# Arduino_1_0.net
KiCad netlist of a schematic drawn in EAGLE
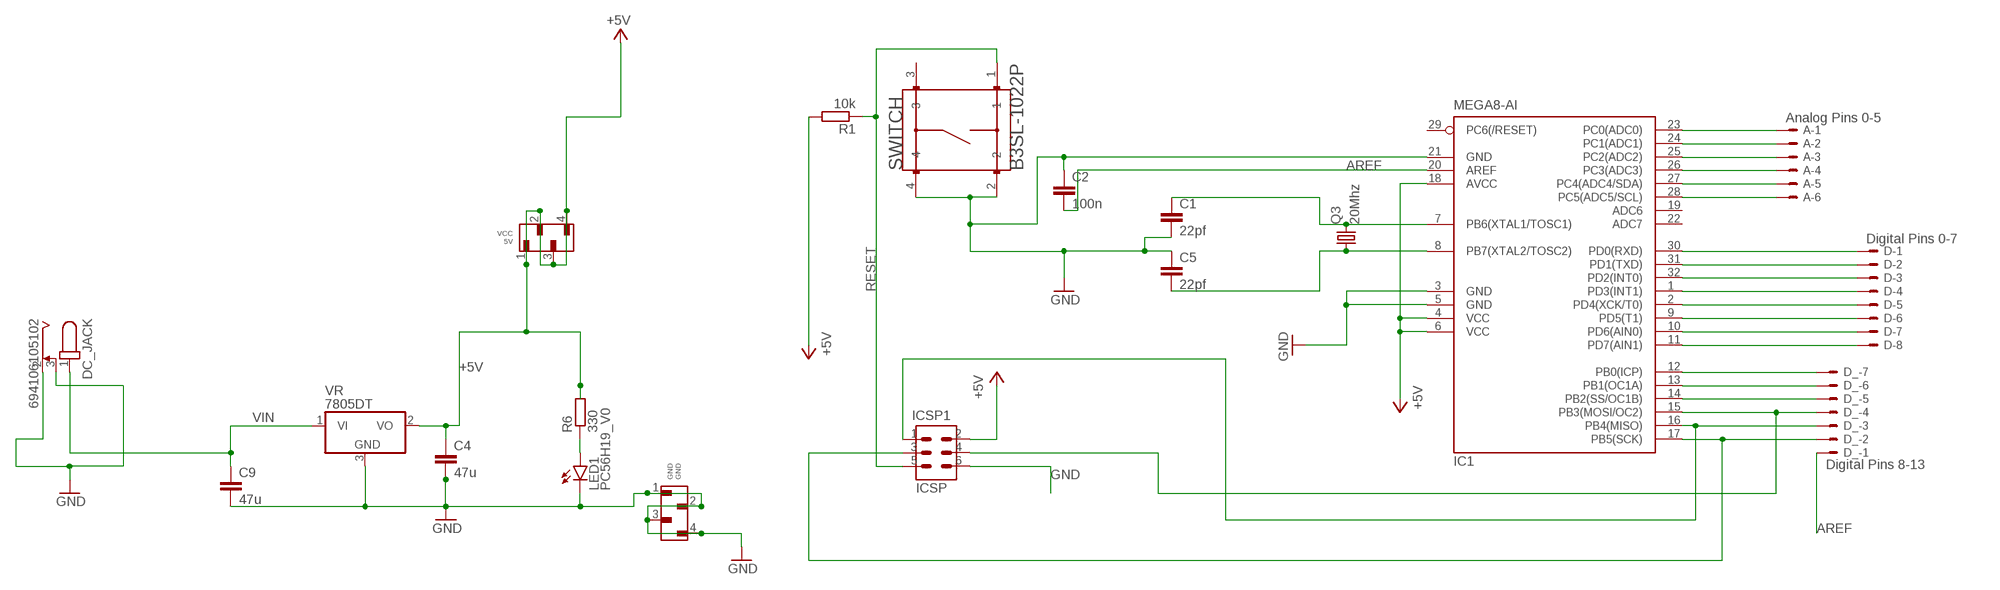
[diagram p0: schematic, sheet 1]

(export (version "E")
  (design (tool "Eeschema 10.0.6"))
  (components
    (comp (ref "A")
      (value "Analog Pins 0-5")
      (footprint "eagle-import:87438-06")
      (fields (field (name "MF") "MOLEX") (field (name "MPN") "87438-0643"))
      (libsource (lib "eagle-import") (part "87438-06"))
    )
    (comp (ref "C1")
      (value "22pf")
      (footprint "eagle-import:C0805")
      (libsource (lib "eagle-import") (part "C-EUC0805"))
    )
    (comp (ref "C2")
      (value "100n")
      (footprint "eagle-import:C0805")
      (libsource (lib "eagle-import") (part "C-EUC0805"))
    )
    (comp (ref "C4")
      (value "47u")
      (footprint "eagle-import:C0805")
      (libsource (lib "eagle-import") (part "C-EUC0805"))
    )
    (comp (ref "C5")
      (value "22pf")
      (footprint "eagle-import:C0805")
      (libsource (lib "eagle-import") (part "C-EUC0805"))
    )
    (comp (ref "C9")
      (value "47u")
      (footprint "eagle-import:C0805")
      (libsource (lib "eagle-import") (part "C-EUC0805"))
    )
    (comp (ref "D")
      (value "Digital Pins 0-7")
      (footprint "eagle-import:87438-08")
      (fields (field (name "MF") "MOLEX"))
      (libsource (lib "eagle-import") (part "87438-08"))
    )
    (comp (ref "DC_JACK")
      (value "694106105102")
      (footprint "eagle-import:694106105102")
      (fields
        (field (name "DIGIKEY_PART_NUMBER") "732-5928-2-ND")
        (field (name "MANUFACTURER") "Wurth Electronics Inc.")
        (field (name "CREATED_BY") "PCBLayout.com")
      )
      (libsource (lib "eagle-import") (part "694106105102"))
    )
    (comp (ref "D_")
      (value "Digital Pins 8-13")
      (footprint "eagle-import:87438-07")
      (fields (field (name "MF") "WALDOM/MOLEX") (field (name "MPN") "87438-0733"))
      (libsource (lib "eagle-import") (part "87438-07"))
    )
    (comp (ref "GND")
      (value "GND")
      (footprint "eagle-import:61000418221")
      (libsource (lib "eagle-import") (part "6100XX18221_61000418221"))
    )
    (comp (ref "IC1")
      (value "MEGA8-AI")
      (footprint "eagle-import:TQFP32-08")
      (fields (field (name "MPN") "ATMEGA8-16AU"))
      (libsource (lib "eagle-import") (part "MEGA8-AI"))
    )
    (comp (ref "ICSP1")
      (value "ICSP")
      (footprint "eagle-import:621006245821")
      (fields
        (field (name "MANUFACTURER") "Wurth Elektronik")
        (field (name "MPN") "621006245821")
        (field (name "CREATED_BY") "PCBLayout.com")
      )
      (libsource (lib "eagle-import") (part "621006245821"))
    )
    (comp (ref "LED1")
      (value "PC56H19_V0")
      (footprint "eagle-import:PC56H19_V0")
      (libsource (lib "eagle-import") (part "PC56H19_V0"))
    )
    (comp (ref "Q3")
      (value "20Mhz")
      (footprint "eagle-import:FC-12M")
      (libsource (lib "eagle-import") (part "FC-12M"))
    )
    (comp (ref "R1")
      (value "10k")
      (footprint "eagle-import:M0805")
      (libsource (lib "eagle-import") (part "R-EU_M0805"))
    )
    (comp (ref "R6")
      (value "330")
      (footprint "eagle-import:M0805")
      (libsource (lib "eagle-import") (part "R-EU_M0805"))
    )
    (comp (ref "SWITCH")
      (value "B3SL-1022P")
      (footprint "eagle-import:SW_B3SL-1022P")
      (fields (field (name "MF") "Omron"))
      (libsource (lib "eagle-import") (part "B3SL-1022P"))
    )
    (comp (ref "VCC")
      (value "5V")
      (footprint "eagle-import:61000418221")
      (libsource (lib "eagle-import") (part "6100XX18221_61000418221"))
    )
    (comp (ref "VR")
      (value "7805DT")
      (footprint "eagle-import:TO252")
      (libsource (lib "eagle-import") (part "78DT05"))
    )
  )
  (nets
    (net (code "1") (name "+5V") (class "Default")
      (node (ref "C4") (pin "1") (pinfunction "1_1") (pintype "passive"))
      (node (ref "IC1") (pin "18") (pinfunction "AVCC_18") (pintype "power_in"))
      (node (ref "IC1") (pin "4") (pinfunction "VCC_4") (pintype "power_in"))
      (node (ref "IC1") (pin "6") (pinfunction "VCC_6") (pintype "power_in"))
      (node (ref "ICSP1") (pin "2") (pinfunction "2_2") (pintype "passive"))
      (node (ref "R1") (pin "2") (pinfunction "2_2") (pintype "passive"))
      (node (ref "R6") (pin "2") (pinfunction "2_2") (pintype "passive"))
      (node (ref "VCC") (pin "1") (pinfunction "1_1") (pintype "passive"))
      (node (ref "VCC") (pin "2") (pinfunction "2_2") (pintype "passive"))
      (node (ref "VCC") (pin "3") (pinfunction "3_3") (pintype "passive"))
      (node (ref "VCC") (pin "4") (pinfunction "4_4") (pintype "passive"))
      (node (ref "VR") (pin "2") (pinfunction "VO_2") (pintype "passive"))
    )
    (net (code "2") (name "/AREF") (class "Default")
      (node (ref "C2") (pin "2") (pinfunction "2_2") (pintype "passive"))
      (node (ref "D_") (pin "1") (pinfunction "S_1") (pintype "passive"))
      (node (ref "IC1") (pin "20") (pinfunction "AREF_20") (pintype "passive"))
    )
    (net (code "3") (name "/RESET") (class "Default")
      (node (ref "ICSP1") (pin "5") (pinfunction "5_5") (pintype "passive"))
      (node (ref "R1") (pin "1") (pinfunction "1_1") (pintype "passive"))
      (node (ref "SWITCH") (pin "1") (pinfunction "1_1") (pintype "passive"))
    )
    (net (code "4") (name "/VIN") (class "Default")
      (node (ref "C9") (pin "1") (pinfunction "1_1") (pintype "passive"))
      (node (ref "DC_JACK") (pin "1") (pinfunction "1_1") (pintype "passive"))
      (node (ref "VR") (pin "1") (pinfunction "VI_1") (pintype "input"))
    )
    (net (code "5") (name "GND") (class "Default")
      (node (ref "C1") (pin "2") (pinfunction "2_2") (pintype "passive"))
      (node (ref "C2") (pin "1") (pinfunction "1_1") (pintype "passive"))
      (node (ref "C4") (pin "2") (pinfunction "2_2") (pintype "passive"))
      (node (ref "C5") (pin "1") (pinfunction "1_1") (pintype "passive"))
      (node (ref "C9") (pin "2") (pinfunction "2_2") (pintype "passive"))
      (node (ref "DC_JACK") (pin "2") (pinfunction "2_2") (pintype "passive"))
      (node (ref "DC_JACK") (pin "3") (pinfunction "3_3") (pintype "passive"))
      (node (ref "GND") (pin "1") (pinfunction "1_1") (pintype "passive"))
      (node (ref "GND") (pin "2") (pinfunction "2_2") (pintype "passive"))
      (node (ref "GND") (pin "3") (pinfunction "3_3") (pintype "passive"))
      (node (ref "GND") (pin "4") (pinfunction "4_4") (pintype "passive"))
      (node (ref "IC1") (pin "21") (pinfunction "GND_21") (pintype "power_in"))
      (node (ref "IC1") (pin "3") (pinfunction "GND_3") (pintype "power_in"))
      (node (ref "IC1") (pin "5") (pinfunction "GND_5") (pintype "power_in"))
      (node (ref "ICSP1") (pin "6") (pinfunction "6_6") (pintype "passive"))
      (node (ref "LED1") (pin "1") (pinfunction "C_1") (pintype "passive"))
      (node (ref "LED1") (pin "3") (pinfunction "C_3") (pintype "passive"))
      (node (ref "SWITCH") (pin "2") (pinfunction "2_2") (pintype "passive"))
      (node (ref "SWITCH") (pin "4") (pinfunction "4_4") (pintype "passive"))
      (node (ref "VR") (pin "3") (pinfunction "GND_3") (pintype "passive"))
    )
    (net (code "6") (name "Net-(AA-S)") (class "Default")
      (node (ref "A") (pin "1") (pinfunction "S_1") (pintype "passive"))
      (node (ref "IC1") (pin "23") (pinfunction "PC0(ADC0)_23") (pintype "bidirectional"))
    )
    (net (code "7") (name "Net-(AB-S)") (class "Default")
      (node (ref "A") (pin "2") (pinfunction "S_2") (pintype "passive"))
      (node (ref "IC1") (pin "24") (pinfunction "PC1(ADC1)_24") (pintype "bidirectional"))
    )
    (net (code "8") (name "Net-(AC-S)") (class "Default")
      (node (ref "A") (pin "3") (pinfunction "S_3") (pintype "passive"))
      (node (ref "IC1") (pin "25") (pinfunction "PC2(ADC2)_25") (pintype "bidirectional"))
    )
    (net (code "9") (name "Net-(AD-S)") (class "Default")
      (node (ref "A") (pin "4") (pinfunction "S_4") (pintype "passive"))
      (node (ref "IC1") (pin "26") (pinfunction "PC3(ADC3)_26") (pintype "bidirectional"))
    )
    (net (code "10") (name "Net-(AE-S)") (class "Default")
      (node (ref "A") (pin "5") (pinfunction "S_5") (pintype "passive"))
      (node (ref "IC1") (pin "27") (pinfunction "PC4(ADC4/SDA)_27") (pintype "bidirectional"))
    )
    (net (code "11") (name "Net-(AF-S)") (class "Default")
      (node (ref "A") (pin "6") (pinfunction "S_6") (pintype "passive"))
      (node (ref "IC1") (pin "28") (pinfunction "PC5(ADC5/SCL)_28") (pintype "bidirectional"))
    )
    (net (code "12") (name "Net-(DA-S)") (class "Default")
      (node (ref "D") (pin "1") (pinfunction "S_1") (pintype "passive"))
      (node (ref "IC1") (pin "30") (pinfunction "PD0(RXD)_30") (pintype "bidirectional"))
    )
    (net (code "13") (name "Net-(DB-S)") (class "Default")
      (node (ref "D") (pin "2") (pinfunction "S_2") (pintype "passive"))
      (node (ref "IC1") (pin "31") (pinfunction "PD1(TXD)_31") (pintype "bidirectional"))
    )
    (net (code "14") (name "Net-(DC-S)") (class "Default")
      (node (ref "D") (pin "3") (pinfunction "S_3") (pintype "passive"))
      (node (ref "IC1") (pin "32") (pinfunction "PD2(INT0)_32") (pintype "bidirectional"))
    )
    (net (code "15") (name "Net-(DD-S)") (class "Default")
      (node (ref "D") (pin "4") (pinfunction "S_4") (pintype "passive"))
      (node (ref "IC1") (pin "1") (pinfunction "PD3(INT1)_1") (pintype "bidirectional"))
    )
    (net (code "16") (name "Net-(DE-S)") (class "Default")
      (node (ref "D") (pin "5") (pinfunction "S_5") (pintype "passive"))
      (node (ref "IC1") (pin "2") (pinfunction "PD4(XCK/T0)_2") (pintype "bidirectional"))
    )
    (net (code "17") (name "Net-(DF-S)") (class "Default")
      (node (ref "D") (pin "6") (pinfunction "S_6") (pintype "passive"))
      (node (ref "IC1") (pin "9") (pinfunction "PD5(T1)_9") (pintype "bidirectional"))
    )
    (net (code "18") (name "Net-(DG-S)") (class "Default")
      (node (ref "D") (pin "7") (pinfunction "S_7") (pintype "passive"))
      (node (ref "IC1") (pin "10") (pinfunction "PD6(AIN0)_10") (pintype "bidirectional"))
    )
    (net (code "19") (name "Net-(DH-S)") (class "Default")
      (node (ref "D") (pin "8") (pinfunction "S_8") (pintype "passive"))
      (node (ref "IC1") (pin "11") (pinfunction "PD7(AIN1)_11") (pintype "bidirectional"))
    )
    (net (code "20") (name "Net-(D_B-S)") (class "Default")
      (node (ref "D_") (pin "2") (pinfunction "S_2") (pintype "passive"))
      (node (ref "IC1") (pin "17") (pinfunction "PB5(SCK)_17") (pintype "bidirectional"))
      (node (ref "ICSP1") (pin "3") (pinfunction "3_3") (pintype "passive"))
    )
    (net (code "21") (name "Net-(D_C-S)") (class "Default")
      (node (ref "D_") (pin "3") (pinfunction "S_3") (pintype "passive"))
      (node (ref "IC1") (pin "16") (pinfunction "PB4(MISO)_16") (pintype "bidirectional"))
      (node (ref "ICSP1") (pin "1") (pinfunction "1_1") (pintype "passive"))
    )
    (net (code "22") (name "Net-(D_D-S)") (class "Default")
      (node (ref "D_") (pin "4") (pinfunction "S_4") (pintype "passive"))
      (node (ref "IC1") (pin "15") (pinfunction "PB3(MOSI/OC2)_15") (pintype "bidirectional"))
      (node (ref "ICSP1") (pin "4") (pinfunction "4_4") (pintype "passive"))
    )
    (net (code "23") (name "Net-(D_E-S)") (class "Default")
      (node (ref "D_") (pin "5") (pinfunction "S_5") (pintype "passive"))
      (node (ref "IC1") (pin "14") (pinfunction "PB2(SS/OC1B)_14") (pintype "bidirectional"))
    )
    (net (code "24") (name "Net-(D_F-S)") (class "Default")
      (node (ref "D_") (pin "6") (pinfunction "S_6") (pintype "passive"))
      (node (ref "IC1") (pin "13") (pinfunction "PB1(OC1A)_13") (pintype "bidirectional"))
    )
    (net (code "25") (name "Net-(D_G-S)") (class "Default")
      (node (ref "D_") (pin "7") (pinfunction "S_7") (pintype "passive"))
      (node (ref "IC1") (pin "12") (pinfunction "PB0(ICP)_12") (pintype "bidirectional"))
    )
    (net (code "26") (name "Net-(IC1-PB6(XTAL1{slash}TOSC1))") (class "Default")
      (node (ref "C1") (pin "1") (pinfunction "1_1") (pintype "passive"))
      (node (ref "IC1") (pin "7") (pinfunction "PB6(XTAL1/TOSC1)_7") (pintype "bidirectional"))
      (node (ref "Q3") (pin "2") (pinfunction "2_2") (pintype "passive"))
    )
    (net (code "27") (name "Net-(IC1-PB7(XTAL2{slash}TOSC2))") (class "Default")
      (node (ref "C5") (pin "2") (pinfunction "2_2") (pintype "passive"))
      (node (ref "IC1") (pin "8") (pinfunction "PB7(XTAL2/TOSC2)_8") (pintype "bidirectional"))
      (node (ref "Q3") (pin "1") (pinfunction "1_1") (pintype "passive"))
    )
    (net (code "28") (name "Net-(LED1-A-Pad2)") (class "Default")
      (node (ref "LED1") (pin "2") (pinfunction "A_2") (pintype "passive"))
      (node (ref "LED1") (pin "4") (pinfunction "A_4") (pintype "passive"))
      (node (ref "R6") (pin "1") (pinfunction "1_1") (pintype "passive"))
    )
    (net (code "29") (name "unconnected-(IC1-ADC6-Pad19)") (class "Default")
      (node (ref "IC1") (pin "19") (pinfunction "ADC6_19") (pintype "bidirectional"))
    )
    (net (code "30") (name "unconnected-(IC1-ADC7-Pad22)") (class "Default")
      (node (ref "IC1") (pin "22") (pinfunction "ADC7_22") (pintype "bidirectional"))
    )
    (net (code "31") (name "unconnected-(IC1-PC6({slash}RESET)-Pad29)") (class "Default")
      (node (ref "IC1") (pin "29") (pinfunction "PC6(/RESET)_29") (pintype "bidirectional"))
    )
    (net (code "32") (name "unconnected-(SWITCH-Pad3)") (class "Default")
      (node (ref "SWITCH") (pin "3") (pinfunction "3_3") (pintype "passive"))
    )
  )
)
